# SCH_Sensor-Wind_Altium.net
KiCad netlist of a schematic drawn in Altium Designer
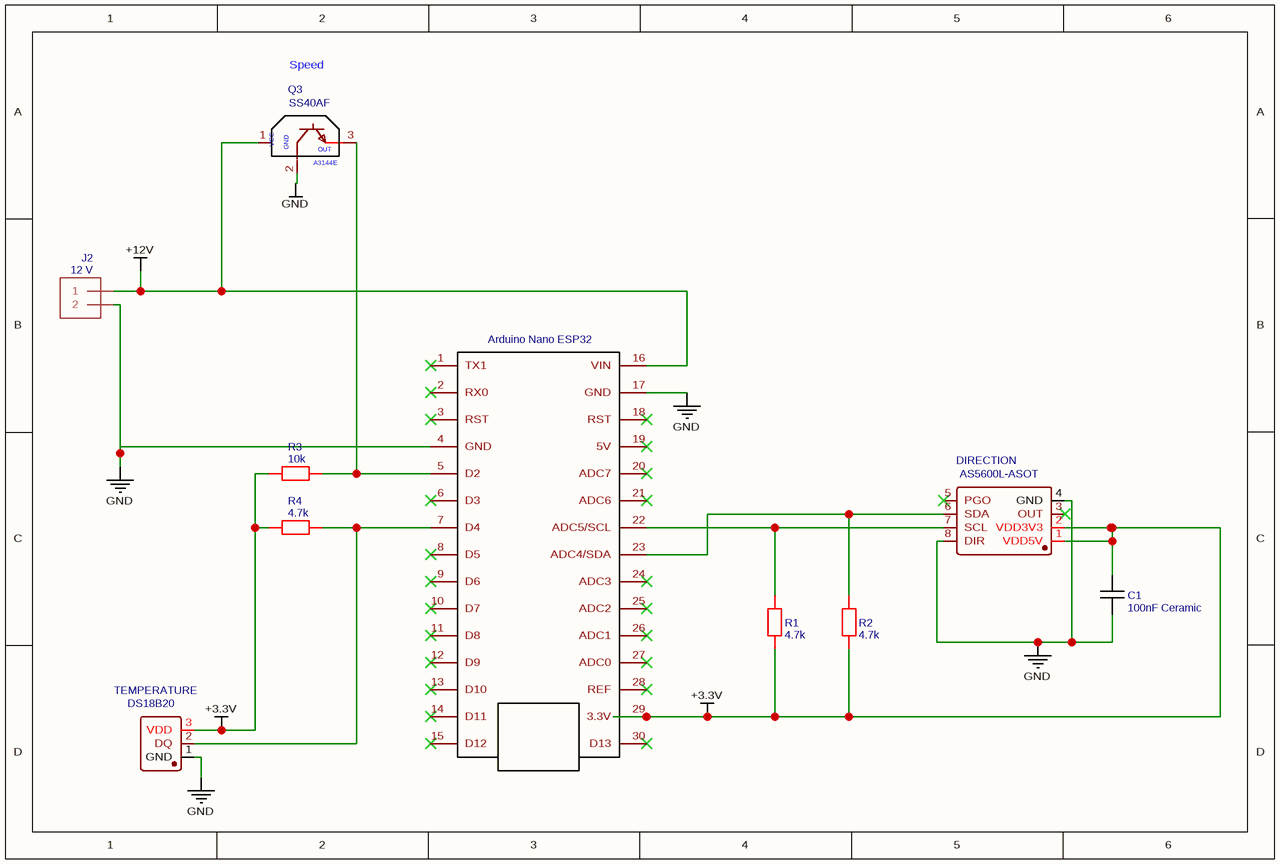
[diagram p0: SCH_Sensor-Wind_Altium.schdoc]

(export (version "E")
  (design (tool "Eeschema 10.0.6"))
  (components
    (comp (ref "C1")
      (value "100nF Ceramic")
      (fields
        (field (name "MANUFACTURER PART") "Capacitor_Ceramic")
        (field (name "CONTRIBUTOR") "huuvinhz755")
      )
      (libsource (lib "altium-import") (part "root_3_100nF Ceramic_"))
    )
    (comp (ref "DIRECTION")
      (value "AS5600L-ASOT")
      (fields (field (name "MANUFACTURER") "美国AMS") (field (name "CONTRIBUTOR") "LCSC"))
      (libsource (lib "altium-import") (part "root_2_AS5600L-ASOT_"))
    )
    (comp (ref "J2")
      (value "12 V")
      (fields (field (name "CONTRIBUTOR") "Adafruit"))
      (libsource (lib "altium-import") (part "root_0_12 V_"))
    )
    (comp (ref "Q3")
      (value "SS40AF")
      (fields (field (name "MANUFACTURER") "Honeywell") (field (name "CONTRIBUTOR") "rakowski.hub"))
      (libsource (lib "altium-import") (part "root_3_SS40AF_"))
    )
    (comp (ref "R1")
      (value "4.7k")
      (fields (field (name "CONTRIBUTOR") "Kagutsuchi"))
      (libsource (lib "altium-import") (part "root_1_4.7k_"))
    )
    (comp (ref "R2")
      (value "4.7k")
      (fields (field (name "CONTRIBUTOR") "Kagutsuchi"))
      (libsource (lib "altium-import") (part "root_1_4.7k_"))
    )
    (comp (ref "R3")
      (value "10k")
      (fields (field (name "CONTRIBUTOR") "Kagutsuchi"))
      (libsource (lib "altium-import") (part "root_0_10k_"))
    )
    (comp (ref "R4")
      (value "4.7k")
      (fields (field (name "CONTRIBUTOR") "Kagutsuchi"))
      (libsource (lib "altium-import") (part "root_0_4.7k_"))
    )
    (comp (ref "TEMPERATURE")
      (value "DS18B20")
      (fields
        (field (name "MANUFACTURER") "Youtai Semiconductor Co., Ltd.")
        (field (name "CONTRIBUTOR") "LCSC")
      )
      (libsource (lib "altium-import") (part "root_2_DS18B20_"))
    )
    (comp (ref "U1")
      (value "Arduino Nano ESP32")
      (fields (field (name "CONTRIBUTOR") "Nikolay Yanev"))
      (libsource (lib "altium-import") (part "root_0_Arduino Nano ESP32_"))
    )
  )
  (nets
    (net (code "1") (name "+3.3V") (class "Default")
      (node (ref "C1") (pin "1") (pinfunction "1_1") (pintype "passive"))
      (node (ref "DIRECTION") (pin "1") (pinfunction "VDD5V_1") (pintype "passive"))
      (node (ref "DIRECTION") (pin "2") (pinfunction "VDD3V3_2") (pintype "passive"))
      (node (ref "R1") (pin "1") (pinfunction "2_1") (pintype "passive"))
      (node (ref "R2") (pin "1") (pinfunction "2_1") (pintype "passive"))
      (node (ref "R3") (pin "1") (pinfunction "2_1") (pintype "passive"))
      (node (ref "R4") (pin "1") (pinfunction "2_1") (pintype "passive"))
      (node (ref "TEMPERATURE") (pin "3") (pinfunction "VDD_3") (pintype "passive"))
      (node (ref "U1") (pin "29") (pinfunction "3.3V_29") (pintype "passive"))
    )
    (net (code "2") (name "+12V") (class "Default")
      (node (ref "J2") (pin "1") (pinfunction "1_1") (pintype "passive"))
      (node (ref "Q3") (pin "1") (pinfunction "Supply_1") (pintype "passive"))
      (node (ref "U1") (pin "16") (pinfunction "VIN_16") (pintype "passive"))
    )
    (net (code "3") (name "GND") (class "Default")
      (node (ref "C1") (pin "2") (pinfunction "2_2") (pintype "passive"))
      (node (ref "DIRECTION") (pin "4") (pinfunction "GND_4") (pintype "passive"))
      (node (ref "DIRECTION") (pin "8") (pinfunction "DIR_8") (pintype "passive"))
      (node (ref "J2") (pin "2") (pinfunction "2_2") (pintype "passive"))
      (node (ref "Q3") (pin "2") (pinfunction "Ground_2") (pintype "passive"))
      (node (ref "TEMPERATURE") (pin "1") (pinfunction "GND_1") (pintype "passive"))
      (node (ref "U1") (pin "17") (pinfunction "GND_17") (pintype "passive"))
      (node (ref "U1") (pin "4") (pinfunction "GND_4") (pintype "passive"))
    )
    (net (code "4") (name "Net-(DIRECTION-SCL)") (class "Default")
      (node (ref "DIRECTION") (pin "7") (pinfunction "SCL_7") (pintype "passive"))
      (node (ref "R1") (pin "2") (pinfunction "1_2") (pintype "passive"))
      (node (ref "U1") (pin "22") (pinfunction "ADC5/SCL_22") (pintype "passive"))
    )
    (net (code "5") (name "Net-(DIRECTION-SDA)") (class "Default")
      (node (ref "DIRECTION") (pin "6") (pinfunction "SDA_6") (pintype "passive"))
      (node (ref "R2") (pin "2") (pinfunction "1_2") (pintype "passive"))
      (node (ref "U1") (pin "23") (pinfunction "ADC4/SDA_23") (pintype "passive"))
    )
    (net (code "6") (name "Net-(Q3-Output)") (class "Default")
      (node (ref "Q3") (pin "3") (pinfunction "Output_3") (pintype "passive"))
      (node (ref "R3") (pin "2") (pinfunction "1_2") (pintype "passive"))
      (node (ref "U1") (pin "5") (pinfunction "D2_5") (pintype "passive"))
    )
    (net (code "7") (name "Net-(R4-1)") (class "Default")
      (node (ref "R4") (pin "2") (pinfunction "1_2") (pintype "passive"))
      (node (ref "TEMPERATURE") (pin "2") (pinfunction "DQ_2") (pintype "passive"))
      (node (ref "U1") (pin "7") (pinfunction "D4_7") (pintype "passive"))
    )
    (net (code "8") (name "unconnected-(DIRECTION-OUT-Pad3)") (class "Default")
      (node (ref "DIRECTION") (pin "3") (pinfunction "OUT_3") (pintype "passive+no_connect"))
    )
    (net (code "9") (name "unconnected-(DIRECTION-PGO-Pad5)") (class "Default")
      (node (ref "DIRECTION") (pin "5") (pinfunction "PGO_5") (pintype "passive+no_connect"))
    )
    (net (code "10") (name "unconnected-(U1-5V-Pad19)") (class "Default")
      (node (ref "U1") (pin "19") (pinfunction "5V_19") (pintype "passive+no_connect"))
    )
    (net (code "11") (name "unconnected-(U1-ADC0-Pad27)") (class "Default")
      (node (ref "U1") (pin "27") (pinfunction "ADC0_27") (pintype "passive+no_connect"))
    )
    (net (code "12") (name "unconnected-(U1-ADC1-Pad26)") (class "Default")
      (node (ref "U1") (pin "26") (pinfunction "ADC1_26") (pintype "passive+no_connect"))
    )
    (net (code "13") (name "unconnected-(U1-ADC2-Pad25)") (class "Default")
      (node (ref "U1") (pin "25") (pinfunction "ADC2_25") (pintype "passive+no_connect"))
    )
    (net (code "14") (name "unconnected-(U1-ADC3-Pad24)") (class "Default")
      (node (ref "U1") (pin "24") (pinfunction "ADC3_24") (pintype "passive+no_connect"))
    )
    (net (code "15") (name "unconnected-(U1-ADC6-Pad21)") (class "Default")
      (node (ref "U1") (pin "21") (pinfunction "ADC6_21") (pintype "passive+no_connect"))
    )
    (net (code "16") (name "unconnected-(U1-ADC7-Pad20)") (class "Default")
      (node (ref "U1") (pin "20") (pinfunction "ADC7_20") (pintype "passive+no_connect"))
    )
    (net (code "17") (name "unconnected-(U1-D3-Pad6)") (class "Default")
      (node (ref "U1") (pin "6") (pinfunction "D3_6") (pintype "passive+no_connect"))
    )
    (net (code "18") (name "unconnected-(U1-D5-Pad8)") (class "Default")
      (node (ref "U1") (pin "8") (pinfunction "D5_8") (pintype "passive+no_connect"))
    )
    (net (code "19") (name "unconnected-(U1-D6-Pad9)") (class "Default")
      (node (ref "U1") (pin "9") (pinfunction "D6_9") (pintype "passive+no_connect"))
    )
    (net (code "20") (name "unconnected-(U1-D7-Pad10)") (class "Default")
      (node (ref "U1") (pin "10") (pinfunction "D7_10") (pintype "passive+no_connect"))
    )
    (net (code "21") (name "unconnected-(U1-D8-Pad11)") (class "Default")
      (node (ref "U1") (pin "11") (pinfunction "D8_11") (pintype "passive+no_connect"))
    )
    (net (code "22") (name "unconnected-(U1-D9-Pad12)") (class "Default")
      (node (ref "U1") (pin "12") (pinfunction "D9_12") (pintype "passive+no_connect"))
    )
    (net (code "23") (name "unconnected-(U1-D10-Pad13)") (class "Default")
      (node (ref "U1") (pin "13") (pinfunction "D10_13") (pintype "passive+no_connect"))
    )
    (net (code "24") (name "unconnected-(U1-D11-Pad14)") (class "Default")
      (node (ref "U1") (pin "14") (pinfunction "D11_14") (pintype "passive+no_connect"))
    )
    (net (code "25") (name "unconnected-(U1-D12-Pad15)") (class "Default")
      (node (ref "U1") (pin "15") (pinfunction "D12_15") (pintype "passive+no_connect"))
    )
    (net (code "26") (name "unconnected-(U1-D13-Pad30)") (class "Default")
      (node (ref "U1") (pin "30") (pinfunction "D13_30") (pintype "passive+no_connect"))
    )
    (net (code "27") (name "unconnected-(U1-REF-Pad28)") (class "Default")
      (node (ref "U1") (pin "28") (pinfunction "REF_28") (pintype "passive+no_connect"))
    )
    (net (code "28") (name "unconnected-(U1-RST-Pad3)") (class "Default")
      (node (ref "U1") (pin "3") (pinfunction "RST_3") (pintype "passive+no_connect"))
    )
    (net (code "29") (name "unconnected-(U1-RST-Pad18)") (class "Default")
      (node (ref "U1") (pin "18") (pinfunction "RST_18") (pintype "passive+no_connect"))
    )
    (net (code "30") (name "unconnected-(U1-RX0-Pad2)") (class "Default")
      (node (ref "U1") (pin "2") (pinfunction "RX0_2") (pintype "passive+no_connect"))
    )
    (net (code "31") (name "unconnected-(U1-TX1-Pad1)") (class "Default")
      (node (ref "U1") (pin "1") (pinfunction "TX1_1") (pintype "passive+no_connect"))
    )
  )
)
